# paneControl.net
KiCad netlist of a schematic drawn in EAGLE
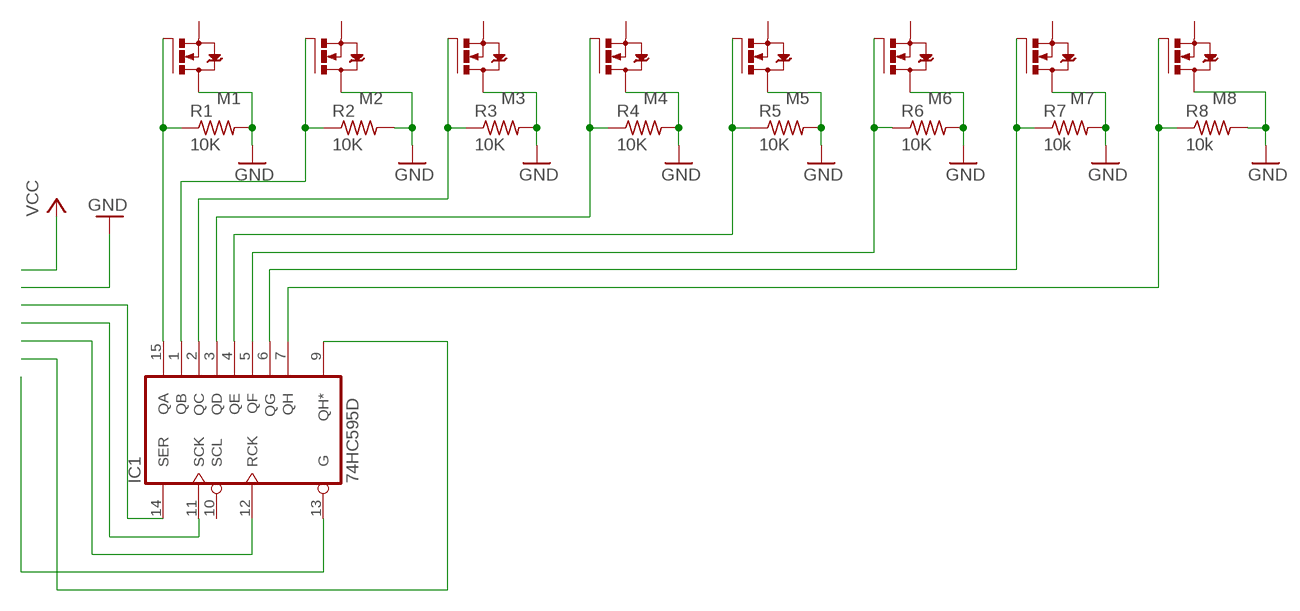
[diagram p0: schematic, sheet 1]

(export (version "E")
  (design (tool "Eeschema 10.0.6"))
  (components
    (comp (ref "IC1")
      (value "74HC595D")
      (footprint "eagle-import:SO16")
      (libsource (lib "eagle-import") (part "74595DHC"))
    )
    (comp (ref "M1")
      (value "2N7000")
      (footprint "eagle-import:TO92D-")
      (libsource (lib "eagle-import") (part "2N7000"))
    )
    (comp (ref "M2")
      (value "2N7000")
      (footprint "eagle-import:TO92D-")
      (libsource (lib "eagle-import") (part "2N7000"))
    )
    (comp (ref "M3")
      (value "2N7000")
      (footprint "eagle-import:TO92D-")
      (libsource (lib "eagle-import") (part "2N7000"))
    )
    (comp (ref "M4")
      (value "2N7000")
      (footprint "eagle-import:TO92D-")
      (libsource (lib "eagle-import") (part "2N7000"))
    )
    (comp (ref "M5")
      (value "2N7000")
      (footprint "eagle-import:TO92D-")
      (libsource (lib "eagle-import") (part "2N7000"))
    )
    (comp (ref "M6")
      (value "2N7000")
      (footprint "eagle-import:TO92D-")
      (libsource (lib "eagle-import") (part "2N7000"))
    )
    (comp (ref "M7")
      (value "2N7000")
      (footprint "eagle-import:TO92D-")
      (libsource (lib "eagle-import") (part "2N7000"))
    )
    (comp (ref "M8")
      (value "2N7000")
      (footprint "eagle-import:TO92D-")
      (libsource (lib "eagle-import") (part "2N7000"))
    )
    (comp (ref "R1")
      (value "10K")
      (footprint "eagle-import:R0603")
      (libsource (lib "eagle-import") (part "R-US_R0603"))
    )
    (comp (ref "R2")
      (value "10K")
      (footprint "eagle-import:R0603")
      (libsource (lib "eagle-import") (part "R-US_R0603"))
    )
    (comp (ref "R3")
      (value "10K")
      (footprint "eagle-import:R0603")
      (libsource (lib "eagle-import") (part "R-US_R0603"))
    )
    (comp (ref "R4")
      (value "10K")
      (footprint "eagle-import:R0603")
      (libsource (lib "eagle-import") (part "R-US_R0603"))
    )
    (comp (ref "R5")
      (value "10K")
      (footprint "eagle-import:R0603")
      (libsource (lib "eagle-import") (part "R-US_R0603"))
    )
    (comp (ref "R6")
      (value "10K")
      (footprint "eagle-import:R0603")
      (libsource (lib "eagle-import") (part "R-US_R0603"))
    )
    (comp (ref "R7")
      (value "10k")
      (footprint "eagle-import:R0603")
      (libsource (lib "eagle-import") (part "R-US_R0603"))
    )
    (comp (ref "R8")
      (value "10k")
      (footprint "eagle-import:R0603")
      (libsource (lib "eagle-import") (part "R-US_R0603"))
    )
  )
  (nets
    (net (code "1") (name "GND") (class "Default")
      (node (ref "M1") (pin "3") (pinfunction "D_3") (pintype "passive"))
      (node (ref "M2") (pin "3") (pinfunction "D_3") (pintype "passive"))
      (node (ref "M3") (pin "3") (pinfunction "D_3") (pintype "passive"))
      (node (ref "M4") (pin "3") (pinfunction "D_3") (pintype "passive"))
      (node (ref "M5") (pin "3") (pinfunction "D_3") (pintype "passive"))
      (node (ref "M6") (pin "3") (pinfunction "D_3") (pintype "passive"))
      (node (ref "M7") (pin "3") (pinfunction "D_3") (pintype "passive"))
      (node (ref "M8") (pin "3") (pinfunction "D_3") (pintype "passive"))
      (node (ref "R1") (pin "2") (pinfunction "2_2") (pintype "passive"))
      (node (ref "R2") (pin "2") (pinfunction "2_2") (pintype "passive"))
      (node (ref "R3") (pin "2") (pinfunction "2_2") (pintype "passive"))
      (node (ref "R4") (pin "2") (pinfunction "2_2") (pintype "passive"))
      (node (ref "R5") (pin "2") (pinfunction "2_2") (pintype "passive"))
      (node (ref "R6") (pin "2") (pinfunction "2_2") (pintype "passive"))
      (node (ref "R7") (pin "2") (pinfunction "2_2") (pintype "passive"))
      (node (ref "R8") (pin "2") (pinfunction "2_2") (pintype "passive"))
    )
    (net (code "2") (name "Net-(IC1A-QA)") (class "Default")
      (node (ref "IC1") (pin "15") (pinfunction "QA_15") (pintype "tri_state"))
      (node (ref "M1") (pin "2") (pinfunction "G_2") (pintype "passive"))
      (node (ref "R1") (pin "1") (pinfunction "1_1") (pintype "passive"))
    )
    (net (code "3") (name "Net-(IC1A-QB)") (class "Default")
      (node (ref "IC1") (pin "1") (pinfunction "QB_1") (pintype "tri_state"))
      (node (ref "M2") (pin "2") (pinfunction "G_2") (pintype "passive"))
      (node (ref "R2") (pin "1") (pinfunction "1_1") (pintype "passive"))
    )
    (net (code "4") (name "Net-(IC1A-QC)") (class "Default")
      (node (ref "IC1") (pin "2") (pinfunction "QC_2") (pintype "tri_state"))
      (node (ref "M3") (pin "2") (pinfunction "G_2") (pintype "passive"))
      (node (ref "R3") (pin "1") (pinfunction "1_1") (pintype "passive"))
    )
    (net (code "5") (name "Net-(IC1A-QD)") (class "Default")
      (node (ref "IC1") (pin "3") (pinfunction "QD_3") (pintype "tri_state"))
      (node (ref "M4") (pin "2") (pinfunction "G_2") (pintype "passive"))
      (node (ref "R4") (pin "1") (pinfunction "1_1") (pintype "passive"))
    )
    (net (code "6") (name "Net-(IC1A-QE)") (class "Default")
      (node (ref "IC1") (pin "4") (pinfunction "QE_4") (pintype "tri_state"))
      (node (ref "M5") (pin "2") (pinfunction "G_2") (pintype "passive"))
      (node (ref "R5") (pin "1") (pinfunction "1_1") (pintype "passive"))
    )
    (net (code "7") (name "Net-(IC1A-QF)") (class "Default")
      (node (ref "IC1") (pin "5") (pinfunction "QF_5") (pintype "tri_state"))
      (node (ref "M6") (pin "2") (pinfunction "G_2") (pintype "passive"))
      (node (ref "R6") (pin "1") (pinfunction "1_1") (pintype "passive"))
    )
    (net (code "8") (name "Net-(IC1A-QG)") (class "Default")
      (node (ref "IC1") (pin "6") (pinfunction "QG_6") (pintype "tri_state"))
      (node (ref "M7") (pin "2") (pinfunction "G_2") (pintype "passive"))
      (node (ref "R7") (pin "1") (pinfunction "1_1") (pintype "passive"))
    )
    (net (code "9") (name "Net-(IC1A-QH)") (class "Default")
      (node (ref "IC1") (pin "7") (pinfunction "QH_7") (pintype "tri_state"))
      (node (ref "M8") (pin "2") (pinfunction "G_2") (pintype "passive"))
      (node (ref "R8") (pin "1") (pinfunction "1_1") (pintype "passive"))
    )
    (net (code "11") (name "unconnected-(IC1A-G-Pad13)") (class "Default")
      (node (ref "IC1") (pin "13") (pinfunction "G_13") (pintype "input"))
    )
    (net (code "12") (name "unconnected-(IC1A-QH*-Pad9)") (class "Default")
      (node (ref "IC1") (pin "9") (pinfunction "QH*_9") (pintype "tri_state"))
    )
    (net (code "13") (name "unconnected-(IC1A-RCK-Pad12)") (class "Default")
      (node (ref "IC1") (pin "12") (pinfunction "RCK_12") (pintype "input"))
    )
    (net (code "14") (name "unconnected-(IC1A-SCK-Pad11)") (class "Default")
      (node (ref "IC1") (pin "11") (pinfunction "SCK_11") (pintype "input"))
    )
    (net (code "15") (name "unconnected-(IC1A-SCL-Pad10)") (class "Default")
      (node (ref "IC1") (pin "10") (pinfunction "SCL_10") (pintype "input"))
    )
    (net (code "16") (name "unconnected-(IC1A-SER-Pad14)") (class "Default")
      (node (ref "IC1") (pin "14") (pinfunction "SER_14") (pintype "input"))
    )
    (net (code "17") (name "unconnected-(M1-S-Pad1)") (class "Default")
      (node (ref "M1") (pin "1") (pinfunction "S_1") (pintype "passive"))
    )
    (net (code "18") (name "unconnected-(M2-S-Pad1)") (class "Default")
      (node (ref "M2") (pin "1") (pinfunction "S_1") (pintype "passive"))
    )
    (net (code "19") (name "unconnected-(M3-S-Pad1)") (class "Default")
      (node (ref "M3") (pin "1") (pinfunction "S_1") (pintype "passive"))
    )
    (net (code "20") (name "unconnected-(M4-S-Pad1)") (class "Default")
      (node (ref "M4") (pin "1") (pinfunction "S_1") (pintype "passive"))
    )
    (net (code "21") (name "unconnected-(M5-S-Pad1)") (class "Default")
      (node (ref "M5") (pin "1") (pinfunction "S_1") (pintype "passive"))
    )
    (net (code "22") (name "unconnected-(M6-S-Pad1)") (class "Default")
      (node (ref "M6") (pin "1") (pinfunction "S_1") (pintype "passive"))
    )
    (net (code "23") (name "unconnected-(M7-S-Pad1)") (class "Default")
      (node (ref "M7") (pin "1") (pinfunction "S_1") (pintype "passive"))
    )
    (net (code "24") (name "unconnected-(M8-S-Pad1)") (class "Default")
      (node (ref "M8") (pin "1") (pinfunction "S_1") (pintype "passive"))
    )
  )
)
